# Measure.net
KiCad netlist of a schematic drawn in Altium Designer
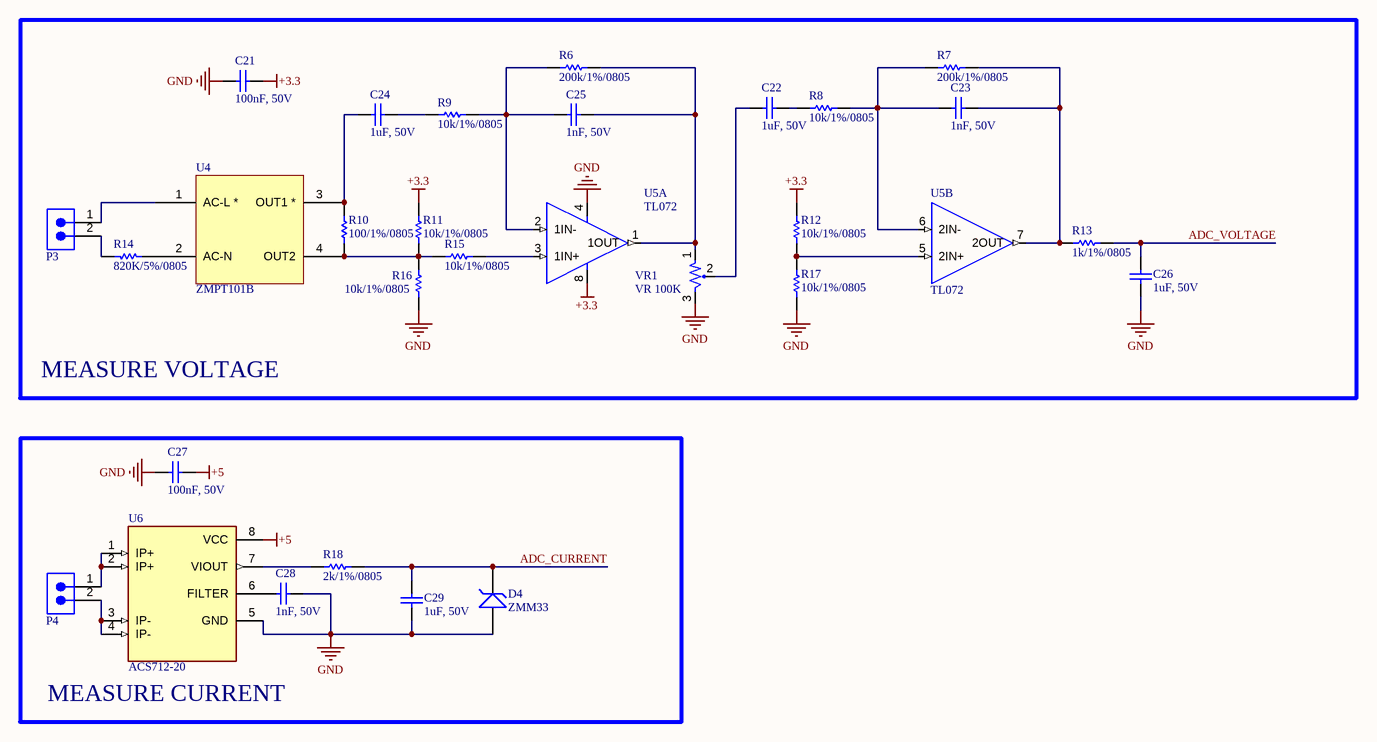
[diagram p0: Measure.SchDoc]

(export (version "E")
  (design (tool "Eeschema 10.0.6"))
  (components
    (comp (ref "C21")
      (value "100nF, 50V")
      (footprint "WCAP-CSGP_0805_H=0.8mm_Wave")
      (description "WCAP-CSGP Multilayer Ceramic Chip Capacitor, General Purpose, size 0805, X7R, 100nF, 50V")
      (fields
        (field (name "MANUFACTURER PART NUMBER") "885012207098")
        (field (name "MANUFACTURER") "Wurth Elektronik")
      )
      (libsource (lib "Altium_WCAP-CSGP (rev20a)") (part "885012207098"))
    )
    (comp (ref "C22")
      (value "1uF, 50V")
      (footprint "WCAP-CSGP_0805_H=1.25mm")
      (description "WCAP-CSGP Multilayer Ceramic Chip Capacitor, General Purpose, size 0805, X7R, 1uF, 50V")
      (fields
        (field (name "MANUFACTURER PART NUMBER") "885012207103")
        (field (name "MANUFACTURER") "Wurth Elektronik")
      )
      (libsource (lib "Altium_WCAP-CSGP (rev20a)") (part "885012207103"))
    )
    (comp (ref "C23")
      (value "1nF, 50V")
      (footprint "WCAP-CSGP_0805_H=0.8mm_Wave")
      (description "WCAP-CSGP Multilayer Ceramic Chip Capacitor, General Purpose, size 0805, NP0, 1nF, 50V")
      (fields
        (field (name "MANUFACTURER PART NUMBER") "885012007063")
        (field (name "MANUFACTURER") "Wurth Elektronik")
      )
      (libsource (lib "Altium_WCAP-CSGP (rev20a)") (part "885012007063"))
    )
    (comp (ref "C24")
      (value "1uF, 50V")
      (footprint "WCAP-CSGP_0805_H=1.25mm")
      (description "WCAP-CSGP Multilayer Ceramic Chip Capacitor, General Purpose, size 0805, X7R, 1uF, 50V")
      (fields
        (field (name "MANUFACTURER PART NUMBER") "885012207103")
        (field (name "MANUFACTURER") "Wurth Elektronik")
      )
      (libsource (lib "Altium_WCAP-CSGP (rev20a)") (part "885012207103"))
    )
    (comp (ref "C25")
      (value "1nF, 50V")
      (footprint "WCAP-CSGP_0805_H=0.8mm_Wave")
      (description "WCAP-CSGP Multilayer Ceramic Chip Capacitor, General Purpose, size 0805, NP0, 1nF, 50V")
      (fields
        (field (name "MANUFACTURER PART NUMBER") "885012007063")
        (field (name "MANUFACTURER") "Wurth Elektronik")
      )
      (libsource (lib "Altium_WCAP-CSGP (rev20a)") (part "885012007063"))
    )
    (comp (ref "C26")
      (value "1uF, 50V")
      (footprint "WCAP-CSGP_0805_H=1.25mm")
      (description "WCAP-CSGP Multilayer Ceramic Chip Capacitor, General Purpose, size 0805, X7R, 1uF, 50V")
      (fields
        (field (name "MANUFACTURER PART NUMBER") "885012207103")
        (field (name "MANUFACTURER") "Wurth Elektronik")
      )
      (libsource (lib "Altium_WCAP-CSGP (rev20a)") (part "885012207103"))
    )
    (comp (ref "C27")
      (value "100nF, 50V")
      (footprint "WCAP-CSGP_0805_H=0.8mm_Wave")
      (description "WCAP-CSGP Multilayer Ceramic Chip Capacitor, General Purpose, size 0805, X7R, 100nF, 50V")
      (fields
        (field (name "MANUFACTURER PART NUMBER") "885012207098")
        (field (name "MANUFACTURER") "Wurth Elektronik")
      )
      (libsource (lib "Altium_WCAP-CSGP (rev20a)") (part "885012207098"))
    )
    (comp (ref "C28")
      (value "1nF, 50V")
      (footprint "WCAP-CSGP_0805_H=0.8mm_Wave")
      (description "WCAP-CSGP Multilayer Ceramic Chip Capacitor, General Purpose, size 0805, NP0, 1nF, 50V")
      (fields
        (field (name "MANUFACTURER PART NUMBER") "885012007063")
        (field (name "MANUFACTURER") "Wurth Elektronik")
      )
      (libsource (lib "Altium_WCAP-CSGP (rev20a)") (part "885012007063"))
    )
    (comp (ref "C29")
      (value "1uF, 50V")
      (footprint "WCAP-CSGP_0805_H=1.25mm")
      (description "WCAP-CSGP Multilayer Ceramic Chip Capacitor, General Purpose, size 0805, X7R, 1uF, 50V")
      (fields
        (field (name "MANUFACTURER PART NUMBER") "885012207103")
        (field (name "MANUFACTURER") "Wurth Elektronik")
      )
      (libsource (lib "Altium_WCAP-CSGP (rev20a)") (part "885012207103"))
    )
    (comp (ref "D4")
      (value "ZMM33")
      (footprint "SOD-80")
      (description "Diode Zenner")
      (libsource (lib "Giang's Libs") (part "ZMM33"))
    )
    (comp (ref "P3")
      (value "691312710002")
      (footprint "691312710002")
      (description "WR-TBL Series 3127 Open Horizontal PCB Header, THT, pitch 5mm, 2p")
      (fields (field (name "MANUFACTURER") "Wurth Elektronik"))
      (libsource (lib "Altium_WR-TBL (rev23b)") (part "691312710002"))
    )
    (comp (ref "P4")
      (value "691312710002")
      (footprint "691312710002")
      (description "WR-TBL Series 3127 Open Horizontal PCB Header, THT, pitch 5mm, 2p")
      (fields (field (name "MANUFACTURER") "Wurth Elektronik"))
      (libsource (lib "Altium_WR-TBL (rev23b)") (part "691312710002"))
    )
    (comp (ref "R6")
      (value "200k/1%/0805")
      (footprint "RES-SM-0805")
      (description "Resistor")
      (fields (field (name "Comment") "RESISTOR SMD"))
      (libsource (lib "PIF_Library") (part "RESISTOR SMD"))
    )
    (comp (ref "R7")
      (value "200k/1%/0805")
      (footprint "RES-SM-0805")
      (description "Resistor")
      (fields (field (name "Comment") "RESISTOR SMD"))
      (libsource (lib "PIF_Library") (part "RESISTOR SMD"))
    )
    (comp (ref "R8")
      (value "10k/1%/0805")
      (footprint "RES-SM-0805")
      (description "Resistor")
      (fields (field (name "Comment") "RESISTOR SMD"))
      (libsource (lib "PIF_Library") (part "RESISTOR SMD"))
    )
    (comp (ref "R9")
      (value "10k/1%/0805")
      (footprint "RES-SM-0805")
      (description "Resistor")
      (fields (field (name "Comment") "RESISTOR SMD"))
      (libsource (lib "PIF_Library") (part "RESISTOR SMD"))
    )
    (comp (ref "R10")
      (value "100/1%/0805")
      (footprint "RES-SM-0805")
      (description "Resistor")
      (fields (field (name "Comment") "RESISTOR SMD"))
      (libsource (lib "PIF_Library") (part "RESISTOR SMD"))
    )
    (comp (ref "R11")
      (value "10k/1%/0805")
      (footprint "RES-SM-0805")
      (description "Resistor")
      (fields (field (name "Comment") "RESISTOR SMD"))
      (libsource (lib "PIF_Library") (part "RESISTOR SMD"))
    )
    (comp (ref "R12")
      (value "10k/1%/0805")
      (footprint "RES-SM-0805")
      (description "Resistor")
      (fields (field (name "Comment") "RESISTOR SMD"))
      (libsource (lib "PIF_Library") (part "RESISTOR SMD"))
    )
    (comp (ref "R13")
      (value "1k/1%/0805")
      (footprint "RES-SM-0805")
      (description "Resistor")
      (fields (field (name "Comment") "RESISTOR SMD"))
      (libsource (lib "PIF_Library") (part "RESISTOR SMD"))
    )
    (comp (ref "R14")
      (value "820K/5%/0805")
      (footprint "RES-SM-0805")
      (description "Resistor")
      (fields (field (name "Comment") "RESISTOR SMD"))
      (libsource (lib "PIF_Library") (part "RESISTOR SMD"))
    )
    (comp (ref "R15")
      (value "10k/1%/0805")
      (footprint "RES-SM-0805")
      (description "Resistor")
      (fields (field (name "Comment") "RESISTOR SMD"))
      (libsource (lib "PIF_Library") (part "RESISTOR SMD"))
    )
    (comp (ref "R16")
      (value "10k/1%/0805")
      (footprint "RES-SM-0805")
      (description "Resistor")
      (fields (field (name "Comment") "RESISTOR SMD"))
      (libsource (lib "PIF_Library") (part "RESISTOR SMD"))
    )
    (comp (ref "R17")
      (value "10k/1%/0805")
      (footprint "RES-SM-0805")
      (description "Resistor")
      (fields (field (name "Comment") "RESISTOR SMD"))
      (libsource (lib "PIF_Library") (part "RESISTOR SMD"))
    )
    (comp (ref "R18")
      (value "2k/1%/0805")
      (footprint "RES-SM-0805")
      (description "Resistor")
      (fields (field (name "Comment") "RESISTOR SMD"))
      (libsource (lib "PIF_Library") (part "RESISTOR SMD"))
    )
    (comp (ref "U4")
      (value "ZMPT101B")
      (footprint "ZMPT101B")
      (description "Minuscule 2mA/2mA Precision Voltage Transformer")
      (libsource (lib "Giang's Libs") (part "ZMPT101B"))
    )
    (comp (ref "U5")
      (value "TL072")
      (footprint "DIP794W45P254L1060H508Q8")
      (description "J-FET Amplifier 2 Circuit 8-SO")
      (fields (field (name "MF") "STMicroelectronics"))
      (libsource (lib "TL072") (part "TL072"))
    )
    (comp (ref "U6")
      (value "ACS712-20")
      (footprint "SOIC127P600X175-8N")
      (fields (field (name "MF") "Analog Devices"))
      (libsource (lib "ACS712-20") (part "ACS712-20"))
    )
    (comp (ref "VR1")
      (value "VR 100K")
      (footprint "VARISTOR 2")
      (description "Var Resistor")
      (fields (field (name "Comment") "10K"))
      (libsource (lib "PIF_Library") (part "Var Resistor"))
    )
  )
  (nets
    (net (code "1") (name "+3.3") (class "Default")
      (node (ref "C21") (pin "2") (pinfunction "2_2") (pintype "passive"))
      (node (ref "R11") (pin "1") (pinfunction "1_1") (pintype "passive"))
      (node (ref "R12") (pin "1") (pinfunction "1_1") (pintype "passive"))
      (node (ref "U5") (pin "8") (pinfunction "VCC+_8") (pintype "power_in"))
    )
    (net (code "2") (name "+5") (class "Default")
      (node (ref "C27") (pin "2") (pinfunction "2_2") (pintype "passive"))
      (node (ref "U6") (pin "8") (pinfunction "VCC_8") (pintype "power_in"))
    )
    (net (code "3") (name "/ADC_CURRENT") (class "Default")
      (node (ref "C29") (pin "2") (pinfunction "2_2") (pintype "passive"))
      (node (ref "D4") (pin "2") (pinfunction "K_2") (pintype "power_in"))
      (node (ref "R18") (pin "2") (pinfunction "2_2") (pintype "passive"))
    )
    (net (code "4") (name "/ADC_VOLTAGE") (class "Default")
      (node (ref "C26") (pin "2") (pinfunction "2_2") (pintype "passive"))
      (node (ref "R13") (pin "2") (pinfunction "2_2") (pintype "passive"))
    )
    (net (code "5") (name "GND") (class "Default")
      (node (ref "C21") (pin "1") (pinfunction "1_1") (pintype "passive"))
      (node (ref "C26") (pin "1") (pinfunction "1_1") (pintype "passive"))
      (node (ref "C27") (pin "1") (pinfunction "1_1") (pintype "passive"))
      (node (ref "C28") (pin "2") (pinfunction "2_2") (pintype "passive"))
      (node (ref "C29") (pin "1") (pinfunction "1_1") (pintype "passive"))
      (node (ref "D4") (pin "1") (pinfunction "A_1") (pintype "power_in"))
      (node (ref "R16") (pin "1") (pinfunction "1_1") (pintype "passive"))
      (node (ref "R17") (pin "1") (pinfunction "1_1") (pintype "passive"))
      (node (ref "U5") (pin "4") (pinfunction "VCC-_4") (pintype "power_in"))
      (node (ref "U6") (pin "5") (pinfunction "GND_5") (pintype "power_in"))
      (node (ref "VR1") (pin "3") (pinfunction "3_3") (pintype "passive"))
    )
    (net (code "6") (name "Net-(C22-Pad1)") (class "Default")
      (node (ref "C22") (pin "1") (pinfunction "1_1") (pintype "passive"))
      (node (ref "R8") (pin "1") (pinfunction "1_1") (pintype "passive"))
    )
    (net (code "7") (name "Net-(C22-Pad2)") (class "Default")
      (node (ref "C22") (pin "2") (pinfunction "2_2") (pintype "passive"))
      (node (ref "VR1") (pin "2") (pinfunction "2_2") (pintype "passive"))
    )
    (net (code "8") (name "Net-(C24-Pad2)") (class "Default")
      (node (ref "C24") (pin "2") (pinfunction "2_2") (pintype "passive"))
      (node (ref "R9") (pin "1") (pinfunction "1_1") (pintype "passive"))
    )
    (net (code "9") (name "Net-(P3-Pad2)") (class "Default")
      (node (ref "P3") (pin "2") (pinfunction "2_2") (pintype "passive"))
      (node (ref "R14") (pin "2") (pinfunction "2_2") (pintype "passive"))
    )
    (net (code "10") (name "Net-(P4-Pad1)") (class "Default")
      (node (ref "P4") (pin "1") (pinfunction "1_1") (pintype "passive"))
      (node (ref "U6") (pin "1") (pinfunction "IP+_1") (pintype "input"))
      (node (ref "U6") (pin "2") (pinfunction "IP+_2") (pintype "input"))
    )
    (net (code "11") (name "Net-(P4-Pad2)") (class "Default")
      (node (ref "P4") (pin "2") (pinfunction "2_2") (pintype "passive"))
      (node (ref "U6") (pin "3") (pinfunction "IP-_3") (pintype "input"))
      (node (ref "U6") (pin "4") (pinfunction "IP-_4") (pintype "input"))
    )
    (net (code "12") (name "Net-(U4-AC-L_*)") (class "Default")
      (node (ref "P3") (pin "1") (pinfunction "1_1") (pintype "passive"))
      (node (ref "U4") (pin "1") (pinfunction "AC-L_*_1") (pintype "passive"))
    )
    (net (code "13") (name "Net-(U4-AC-N)") (class "Default")
      (node (ref "R14") (pin "1") (pinfunction "1_1") (pintype "passive"))
      (node (ref "U4") (pin "2") (pinfunction "AC-N_2") (pintype "passive"))
    )
    (net (code "14") (name "Net-(U4-OUT1_*)") (class "Default")
      (node (ref "C24") (pin "1") (pinfunction "1_1") (pintype "passive"))
      (node (ref "R10") (pin "1") (pinfunction "1_1") (pintype "passive"))
      (node (ref "U4") (pin "3") (pinfunction "OUT1_*_3") (pintype "passive"))
    )
    (net (code "15") (name "Net-(U4-OUT2)") (class "Default")
      (node (ref "R10") (pin "2") (pinfunction "2_2") (pintype "passive"))
      (node (ref "R11") (pin "2") (pinfunction "2_2") (pintype "passive"))
      (node (ref "R15") (pin "1") (pinfunction "1_1") (pintype "passive"))
      (node (ref "R16") (pin "2") (pinfunction "2_2") (pintype "passive"))
      (node (ref "U4") (pin "4") (pinfunction "OUT2_4") (pintype "passive"))
    )
    (net (code "16") (name "Net-(U5A-1IN+)") (class "Default")
      (node (ref "R15") (pin "2") (pinfunction "2_2") (pintype "passive"))
      (node (ref "U5") (pin "3") (pinfunction "1IN+_3") (pintype "input"))
    )
    (net (code "17") (name "Net-(U5A-1IN-)") (class "Default")
      (node (ref "C25") (pin "1") (pinfunction "1_1") (pintype "passive"))
      (node (ref "R6") (pin "1") (pinfunction "1_1") (pintype "passive"))
      (node (ref "R9") (pin "2") (pinfunction "2_2") (pintype "passive"))
      (node (ref "U5") (pin "2") (pinfunction "1IN-_2") (pintype "input"))
    )
    (net (code "18") (name "Net-(U5A-1OUT)") (class "Default")
      (node (ref "C25") (pin "2") (pinfunction "2_2") (pintype "passive"))
      (node (ref "R6") (pin "2") (pinfunction "2_2") (pintype "passive"))
      (node (ref "U5") (pin "1") (pinfunction "1OUT_1") (pintype "output"))
      (node (ref "VR1") (pin "1") (pinfunction "1_1") (pintype "passive"))
    )
    (net (code "19") (name "Net-(U5B-2IN+)") (class "Default")
      (node (ref "R12") (pin "2") (pinfunction "2_2") (pintype "passive"))
      (node (ref "R17") (pin "2") (pinfunction "2_2") (pintype "passive"))
      (node (ref "U5") (pin "5") (pinfunction "2IN+_5") (pintype "input"))
    )
    (net (code "20") (name "Net-(U5B-2IN-)") (class "Default")
      (node (ref "C23") (pin "2") (pinfunction "2_2") (pintype "passive"))
      (node (ref "R7") (pin "1") (pinfunction "1_1") (pintype "passive"))
      (node (ref "R8") (pin "2") (pinfunction "2_2") (pintype "passive"))
      (node (ref "U5") (pin "6") (pinfunction "2IN-_6") (pintype "input"))
    )
    (net (code "21") (name "Net-(U5B-2OUT)") (class "Default")
      (node (ref "C23") (pin "1") (pinfunction "1_1") (pintype "passive"))
      (node (ref "R13") (pin "1") (pinfunction "1_1") (pintype "passive"))
      (node (ref "R7") (pin "2") (pinfunction "2_2") (pintype "passive"))
      (node (ref "U5") (pin "7") (pinfunction "2OUT_7") (pintype "output"))
    )
    (net (code "22") (name "Net-(U6-FILTER)") (class "Default")
      (node (ref "C28") (pin "1") (pinfunction "1_1") (pintype "passive"))
      (node (ref "U6") (pin "6") (pinfunction "FILTER_6") (pintype "passive"))
    )
    (net (code "23") (name "Net-(U6-VIOUT)") (class "Default")
      (node (ref "R18") (pin "1") (pinfunction "1_1") (pintype "passive"))
      (node (ref "U6") (pin "7") (pinfunction "VIOUT_7") (pintype "output"))
    )
  )
)
